# Etapa_Control.net
KiCad netlist of a schematic drawn in EAGLE
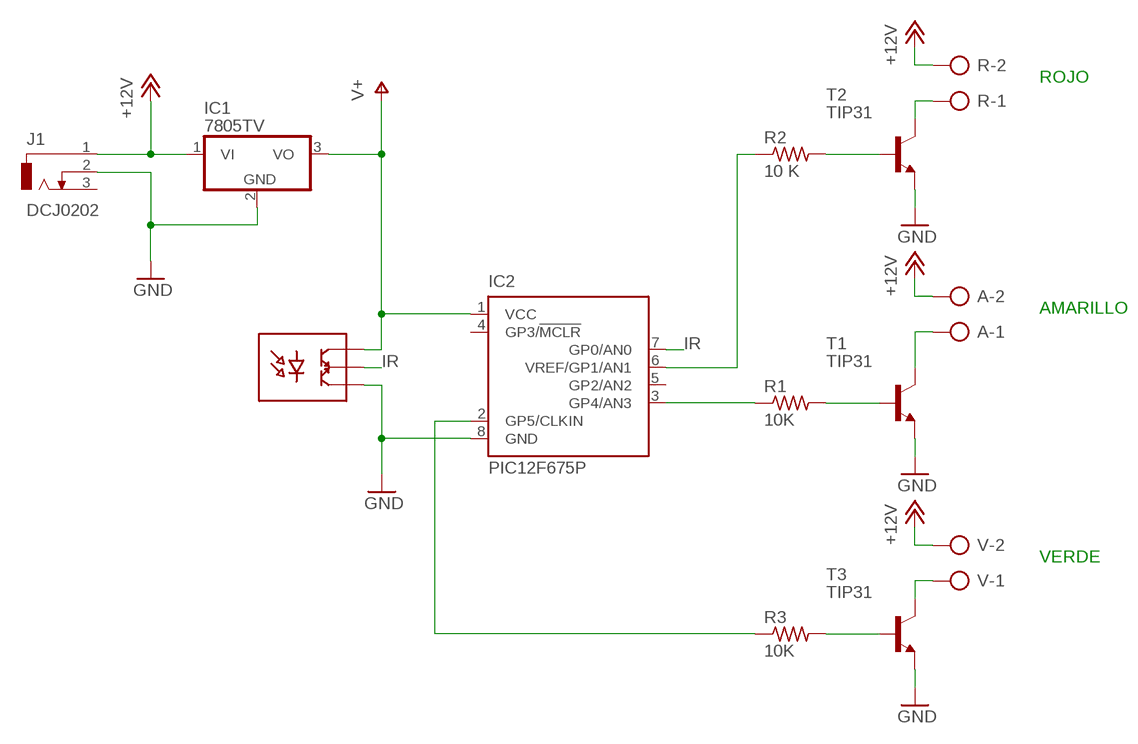
[diagram p0: schematic, sheet 1]

(export (version "E")
  (design (tool "Eeschema 10.0.6"))
  (components
    (comp (ref "A")
      (value "AK300/2")
      (footprint "eagle-import:AK300_2")
      (libsource (lib "eagle-import") (part "AK300/2"))
    )
    (comp (ref "IC1")
      (value "7805TV")
      (footprint "eagle-import:TO220V")
      (libsource (lib "eagle-import") (part "78TV05"))
    )
    (comp (ref "IC2")
      (value "PIC12F675P")
      (footprint "eagle-import:DIL8")
      (fields (field (name "MF") "MICROCHIP") (field (name "MPN") "PIC12F675-E/P"))
      (libsource (lib "eagle-import") (part "PIC12F675P"))
    )
    (comp (ref "J1")
      (value "DCJ0202")
      (footprint "eagle-import:DCJ0202")
      (libsource (lib "eagle-import") (part "DCJ0202"))
    )
    (comp (ref "LF1838")
      (value "LF1838")
      (footprint "eagle-import:LF1838")
      (libsource (lib "eagle-import") (part "LF1838"))
    )
    (comp (ref "R")
      (value "AK300/2")
      (footprint "eagle-import:AK300_2")
      (libsource (lib "eagle-import") (part "AK300/2"))
    )
    (comp (ref "R1")
      (value "10K")
      (footprint "eagle-import:0204_7")
      (libsource (lib "eagle-import") (part "R-US_0204/7"))
    )
    (comp (ref "R2")
      (value "10 K")
      (footprint "eagle-import:0204_7")
      (libsource (lib "eagle-import") (part "R-US_0204/7"))
    )
    (comp (ref "R3")
      (value "10K")
      (footprint "eagle-import:0204_7")
      (libsource (lib "eagle-import") (part "R-US_0204/7"))
    )
    (comp (ref "T1")
      (value "TIP31")
      (footprint "eagle-import:TO220")
      (libsource (lib "eagle-import") (part "TIP31"))
    )
    (comp (ref "T2")
      (value "TIP31")
      (footprint "eagle-import:TO220")
      (libsource (lib "eagle-import") (part "TIP31"))
    )
    (comp (ref "T3")
      (value "TIP31")
      (footprint "eagle-import:TO220")
      (libsource (lib "eagle-import") (part "TIP31"))
    )
    (comp (ref "V")
      (value "AK300/2")
      (footprint "eagle-import:AK300_2")
      (libsource (lib "eagle-import") (part "AK300/2"))
    )
  )
  (nets
    (net (code "1") (name "+12V") (class "Default")
      (node (ref "A") (pin "2") (pinfunction "KL_2") (pintype "passive"))
      (node (ref "IC1") (pin "1") (pinfunction "VI_1") (pintype "input"))
      (node (ref "J1") (pin "1") (pinfunction "1_1") (pintype "passive"))
      (node (ref "R") (pin "2") (pinfunction "KL_2") (pintype "passive"))
      (node (ref "V") (pin "2") (pinfunction "KL_2") (pintype "passive"))
    )
    (net (code "2") (name "/IR") (class "Default")
      (node (ref "IC2") (pin "7") (pinfunction "GP0/AN0_7") (pintype "bidirectional"))
      (node (ref "LF1838") (pin "VOUT") (pinfunction "VOUT_VOUT") (pintype "bidirectional"))
    )
    (net (code "3") (name "GND") (class "Default")
      (node (ref "IC1") (pin "2") (pinfunction "GND_2") (pintype "passive"))
      (node (ref "IC2") (pin "8") (pinfunction "GND_8") (pintype "power_in"))
      (node (ref "J1") (pin "2") (pinfunction "2_2") (pintype "passive"))
      (node (ref "LF1838") (pin "GND") (pinfunction "GND_GND") (pintype "bidirectional"))
      (node (ref "T1") (pin "3") (pinfunction "E_3") (pintype "passive"))
      (node (ref "T2") (pin "3") (pinfunction "E_3") (pintype "passive"))
      (node (ref "T3") (pin "3") (pinfunction "E_3") (pintype "passive"))
    )
    (net (code "4") (name "Net-(AA-KL)") (class "Default")
      (node (ref "A") (pin "1") (pinfunction "KL_1") (pintype "passive"))
      (node (ref "T1") (pin "2") (pinfunction "C_2") (pintype "passive"))
    )
    (net (code "5") (name "Net-(IC2-GP4{slash}AN3)") (class "Default")
      (node (ref "IC2") (pin "3") (pinfunction "GP4/AN3_3") (pintype "bidirectional"))
      (node (ref "R1") (pin "1") (pinfunction "1_1") (pintype "passive"))
    )
    (net (code "6") (name "Net-(IC2-GP5{slash}CLKIN)") (class "Default")
      (node (ref "IC2") (pin "2") (pinfunction "GP5/CLKIN_2") (pintype "bidirectional"))
      (node (ref "R3") (pin "1") (pinfunction "1_1") (pintype "passive"))
    )
    (net (code "7") (name "Net-(IC2-VREF{slash}GP1{slash}AN1)") (class "Default")
      (node (ref "IC2") (pin "6") (pinfunction "VREF/GP1/AN1_6") (pintype "bidirectional"))
      (node (ref "R2") (pin "1") (pinfunction "1_1") (pintype "passive"))
    )
    (net (code "8") (name "Net-(RA-KL)") (class "Default")
      (node (ref "R") (pin "1") (pinfunction "KL_1") (pintype "passive"))
      (node (ref "T2") (pin "2") (pinfunction "C_2") (pintype "passive"))
    )
    (net (code "9") (name "Net-(T1-B)") (class "Default")
      (node (ref "R1") (pin "2") (pinfunction "2_2") (pintype "passive"))
      (node (ref "T1") (pin "1") (pinfunction "B_1") (pintype "passive"))
    )
    (net (code "10") (name "Net-(T2-B)") (class "Default")
      (node (ref "R2") (pin "2") (pinfunction "2_2") (pintype "passive"))
      (node (ref "T2") (pin "1") (pinfunction "B_1") (pintype "passive"))
    )
    (net (code "11") (name "Net-(T3-B)") (class "Default")
      (node (ref "R3") (pin "2") (pinfunction "2_2") (pintype "passive"))
      (node (ref "T3") (pin "1") (pinfunction "B_1") (pintype "passive"))
    )
    (net (code "12") (name "Net-(T3-C)") (class "Default")
      (node (ref "T3") (pin "2") (pinfunction "C_2") (pintype "passive"))
      (node (ref "V") (pin "1") (pinfunction "KL_1") (pintype "passive"))
    )
    (net (code "13") (name "V+") (class "Default")
      (node (ref "IC1") (pin "3") (pinfunction "VO_3") (pintype "passive"))
      (node (ref "IC2") (pin "1") (pinfunction "VCC_1") (pintype "power_in"))
      (node (ref "LF1838") (pin "VCC") (pinfunction "VCC_VCC") (pintype "bidirectional"))
    )
    (net (code "14") (name "unconnected-(IC2-GP2{slash}AN2-Pad5)") (class "Default")
      (node (ref "IC2") (pin "5") (pinfunction "GP2/AN2_5") (pintype "bidirectional"))
    )
    (net (code "15") (name "unconnected-(IC2-GP3{slash}~{MCLR}-Pad4)") (class "Default")
      (node (ref "IC2") (pin "4") (pinfunction "GP3/~{MCLR}_4") (pintype "input"))
    )
    (net (code "16") (name "unconnected-(J1-Pad3)") (class "Default")
      (node (ref "J1") (pin "3") (pinfunction "3_3") (pintype "passive"))
    )
  )
)
